# esp32_radio_sch.net
KiCad netlist of a schematic drawn in Altium Designer
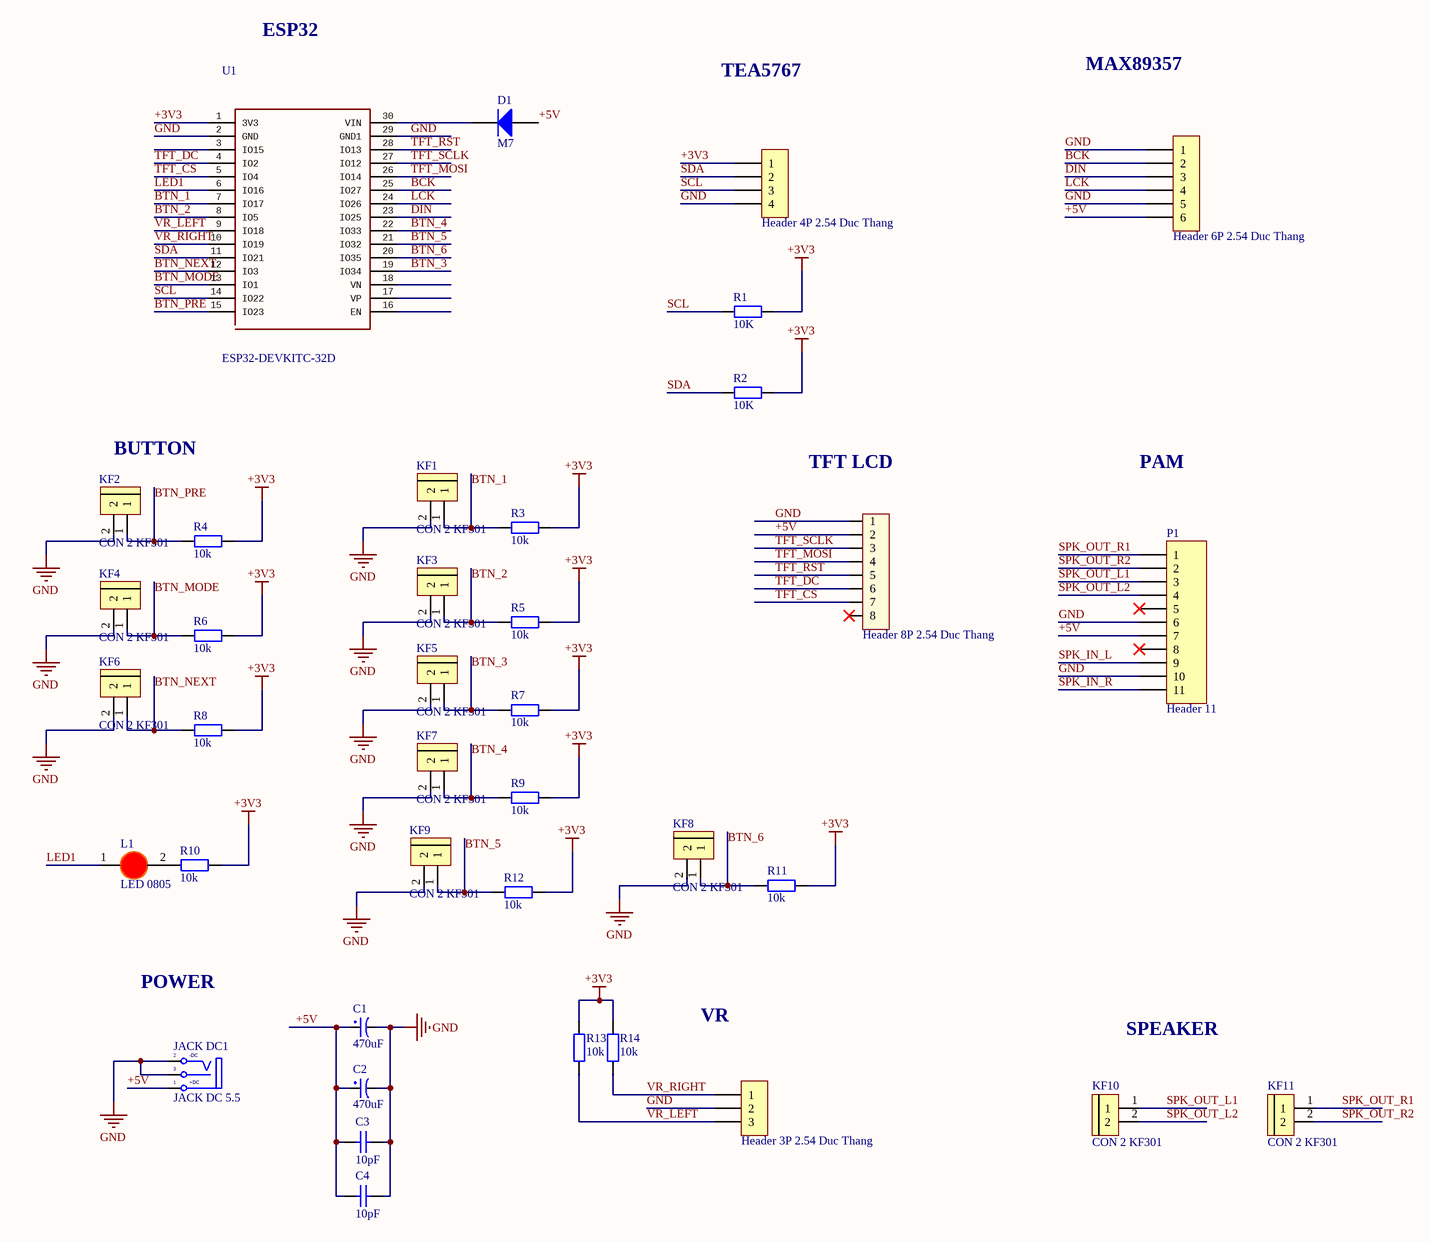
[diagram p0: esp32_radio_sch.SchDoc]

(export (version "E")
  (design (tool "Eeschema 10.0.6"))
  (components
    (comp (ref "C1")
      (value "470uF")
      (footprint "tu tantalum smd7343")
      (description "Dán")
      (libsource (lib "Altium_Lib_by_KhueNguyenCreator") (part "Tu tantalum 470uF 10V SMD7343"))
    )
    (comp (ref "C2")
      (value "470uF")
      (footprint "tu tantalum smd7343")
      (description "Dán")
      (libsource (lib "Altium_Lib_by_KhueNguyenCreator") (part "Tu tantalum 470uF 10V SMD7343"))
    )
    (comp (ref "C3")
      (value "10pF")
      (footprint "tu 0805")
      (description "Dán")
      (libsource (lib "Altium_Lib_by_KhueNguyenCreator") (part "Tu 0805 10pF 50V 10%"))
    )
    (comp (ref "C4")
      (value "10pF")
      (footprint "tu 0805")
      (description "Dán")
      (libsource (lib "Altium_Lib_by_KhueNguyenCreator") (part "Tu 0805 10pF 50V 10%"))
    )
    (comp (ref "D1")
      (value "M7")
      (footprint "DIODE SMA")
      (description "Dán")
      (libsource (lib "Altium_Lib_by_KhueNguyenCreator") (part "Diode M7 ( 4007 )"))
    )
    (comp (ref "H1")
      (value "Header 6P 2.54 Duc Thang")
      (footprint "XH2.54M-6")
      (description "Cắm")
      (libsource (lib "Altium_Lib_by_KhueNguyenCreator") (part "Header 6P 2.54 Duc Thang"))
    )
    (comp (ref "H2")
      (value "Header 4P 2.54 Duc Thang")
      (footprint "XH2.54M-4")
      (description "Cắm")
      (libsource (lib "Altium_Lib_by_KhueNguyenCreator") (part "Header 4P 2.54 Duc Thang"))
    )
    (comp (ref "H3")
      (value "Header 8P 2.54 Duc Thang")
      (footprint "XH2.54M-8")
      (description "Cắm")
      (libsource (lib "Altium_Lib_by_KhueNguyenCreator") (part "Header 8P 2.54 Duc Thang"))
    )
    (comp (ref "H4")
      (value "Header 3P 2.54 Duc Thang")
      (footprint "XH2.54M-3")
      (description "Cắm")
      (libsource (lib "Altium_Lib_by_KhueNguyenCreator") (part "Header 3P 2.54 Duc Thang"))
    )
    (comp (ref "JACK DC1")
      (value "JACK DC 5.5")
      (footprint "JACK DC 5.5")
      (libsource (lib "Altium_Lib_by_KhueNguyenCreator") (part "JACK DC 5.5"))
    )
    (comp (ref "KF1")
      (value "CON 2 KF301")
      (footprint "Nut Nhan 2 Chan SMD 3x6x2.5")
      (description "Cắm")
      (libsource (lib "Altium_Lib_by_KhueNguyenCreator") (part "CON 2 KF301"))
    )
    (comp (ref "KF2")
      (value "CON 2 KF301")
      (footprint "Nut Nhan 2 Chan SMD 3x6x2.5")
      (description "Cắm")
      (libsource (lib "Altium_Lib_by_KhueNguyenCreator") (part "CON 2 KF301"))
    )
    (comp (ref "KF3")
      (value "CON 2 KF301")
      (footprint "Nut Nhan 2 Chan SMD 3x6x2.5")
      (description "Cắm")
      (libsource (lib "Altium_Lib_by_KhueNguyenCreator") (part "CON 2 KF301"))
    )
    (comp (ref "KF4")
      (value "CON 2 KF301")
      (footprint "Nut Nhan 2 Chan SMD 3x6x2.5")
      (description "Cắm")
      (libsource (lib "Altium_Lib_by_KhueNguyenCreator") (part "CON 2 KF301"))
    )
    (comp (ref "KF5")
      (value "CON 2 KF301")
      (footprint "Nut Nhan 2 Chan SMD 3x6x2.5")
      (description "Cắm")
      (libsource (lib "Altium_Lib_by_KhueNguyenCreator") (part "CON 2 KF301"))
    )
    (comp (ref "KF6")
      (value "CON 2 KF301")
      (footprint "Nut Nhan 2 Chan SMD 3x6x2.5")
      (description "Cắm")
      (libsource (lib "Altium_Lib_by_KhueNguyenCreator") (part "CON 2 KF301"))
    )
    (comp (ref "KF7")
      (value "CON 2 KF301")
      (footprint "Nut Nhan 2 Chan SMD 3x6x2.5")
      (description "Cắm")
      (libsource (lib "Altium_Lib_by_KhueNguyenCreator") (part "CON 2 KF301"))
    )
    (comp (ref "KF8")
      (value "CON 2 KF301")
      (footprint "Nut Nhan 2 Chan SMD 3x6x2.5")
      (description "Cắm")
      (libsource (lib "Altium_Lib_by_KhueNguyenCreator") (part "CON 2 KF301"))
    )
    (comp (ref "KF9")
      (value "CON 2 KF301")
      (footprint "Nut Nhan 2 Chan SMD 3x6x2.5")
      (description "Cắm")
      (libsource (lib "Altium_Lib_by_KhueNguyenCreator") (part "CON 2 KF301"))
    )
    (comp (ref "KF10")
      (value "CON 2 KF301")
      (footprint "Con 2 KF301 5.08")
      (description "Cắm")
      (libsource (lib "") (part "CON 2 KF301_1"))
    )
    (comp (ref "KF11")
      (value "CON 2 KF301")
      (footprint "Con 2 KF301 5.08")
      (description "Cắm")
      (libsource (lib "") (part "CON 2 KF301_1"))
    )
    (comp (ref "L1")
      (value "LED 0805")
      (footprint "LED-0805-Red")
      (description "Dán")
      (libsource (lib "Altium_Lib_by_KhueNguyenCreator") (part "LED 0805 Do"))
    )
    (comp (ref "P1")
      (value "Header 11")
      (footprint "Header 11")
      (description "Header, 11-Pin")
      (fields (field (name "PUBLISHER") "Altium Limited"))
      (libsource (lib "Miscellaneous Connectors") (part "Header 11"))
    )
    (comp (ref "R1")
      (value "10K")
      (footprint "tro smd 0805")
      (description "Dán")
      (libsource (lib "Altium_Lib_by_KhueNguyenCreator") (part "Tro 0805 1% 1k"))
    )
    (comp (ref "R2")
      (value "10K")
      (footprint "tro smd 0805")
      (description "Dán")
      (libsource (lib "Altium_Lib_by_KhueNguyenCreator") (part "Tro 0805 1% 1k"))
    )
    (comp (ref "R3")
      (value "10k")
      (footprint "tro smd 0805")
      (description "Dán")
      (libsource (lib "Altium_Lib_by_KhueNguyenCreator") (part "Tro 0805 1% 1k"))
    )
    (comp (ref "R4")
      (value "10k")
      (footprint "tro smd 0805")
      (description "Dán")
      (libsource (lib "Altium_Lib_by_KhueNguyenCreator") (part "Tro 0805 1% 1k"))
    )
    (comp (ref "R5")
      (value "10k")
      (footprint "tro smd 0805")
      (description "Dán")
      (libsource (lib "Altium_Lib_by_KhueNguyenCreator") (part "Tro 0805 1% 1k"))
    )
    (comp (ref "R6")
      (value "10k")
      (footprint "tro smd 0805")
      (description "Dán")
      (libsource (lib "Altium_Lib_by_KhueNguyenCreator") (part "Tro 0805 1% 1k"))
    )
    (comp (ref "R7")
      (value "10k")
      (footprint "tro smd 0805")
      (description "Dán")
      (libsource (lib "Altium_Lib_by_KhueNguyenCreator") (part "Tro 0805 1% 1k"))
    )
    (comp (ref "R8")
      (value "10k")
      (footprint "tro smd 0805")
      (description "Dán")
      (libsource (lib "Altium_Lib_by_KhueNguyenCreator") (part "Tro 0805 1% 1k"))
    )
    (comp (ref "R9")
      (value "10k")
      (footprint "tro smd 0805")
      (description "Dán")
      (libsource (lib "Altium_Lib_by_KhueNguyenCreator") (part "Tro 0805 1% 1k"))
    )
    (comp (ref "R10")
      (value "10k")
      (footprint "tro smd 0805")
      (description "Dán")
      (libsource (lib "Altium_Lib_by_KhueNguyenCreator") (part "Tro 0805 1% 1k"))
    )
    (comp (ref "R11")
      (value "10k")
      (footprint "tro smd 0805")
      (description "Dán")
      (libsource (lib "Altium_Lib_by_KhueNguyenCreator") (part "Tro 0805 1% 1k"))
    )
    (comp (ref "R12")
      (value "10k")
      (footprint "tro smd 0805")
      (description "Dán")
      (libsource (lib "Altium_Lib_by_KhueNguyenCreator") (part "Tro 0805 1% 1k"))
    )
    (comp (ref "R13")
      (value "10k")
      (footprint "tro smd 0805")
      (description "Dán")
      (libsource (lib "Altium_Lib_by_KhueNguyenCreator") (part "Tro 0805 1% 1k"))
    )
    (comp (ref "R14")
      (value "10k")
      (footprint "tro smd 0805")
      (description "Dán")
      (libsource (lib "Altium_Lib_by_KhueNguyenCreator") (part "Tro 0805 1% 1k"))
    )
    (comp (ref "U1")
      (value "ESP32-DEVKITC-32D")
      (footprint "MODULE_ESP32-DEVKITV1")
      (description "Eval Board For Esp-Wroom-32")
      (fields (field (name "MF") "Espressif Systems"))
      (libsource (lib "AltiumLibraryDDT") (part "ESP32-DEVKITC-32D"))
    )
  )
  (nets
    (net (code "1") (name "+3V3") (class "Default")
      (node (ref "H2") (pin "1") (pinfunction "1_1") (pintype "passive"))
      (node (ref "R1") (pin "2") (pinfunction "2_2") (pintype "passive"))
      (node (ref "R10") (pin "2") (pinfunction "2_2") (pintype "passive"))
      (node (ref "R11") (pin "2") (pinfunction "2_2") (pintype "passive"))
      (node (ref "R12") (pin "2") (pinfunction "2_2") (pintype "passive"))
      (node (ref "R13") (pin "2") (pinfunction "2_2") (pintype "passive"))
      (node (ref "R14") (pin "2") (pinfunction "2_2") (pintype "passive"))
      (node (ref "R2") (pin "2") (pinfunction "2_2") (pintype "passive"))
      (node (ref "R3") (pin "2") (pinfunction "2_2") (pintype "passive"))
      (node (ref "R4") (pin "2") (pinfunction "2_2") (pintype "passive"))
      (node (ref "R5") (pin "2") (pinfunction "2_2") (pintype "passive"))
      (node (ref "R6") (pin "2") (pinfunction "2_2") (pintype "passive"))
      (node (ref "R7") (pin "2") (pinfunction "2_2") (pintype "passive"))
      (node (ref "R8") (pin "2") (pinfunction "2_2") (pintype "passive"))
      (node (ref "R9") (pin "2") (pinfunction "2_2") (pintype "passive"))
      (node (ref "U1") (pin "1") (pinfunction "3V3_1") (pintype "passive"))
    )
    (net (code "2") (name "/+5V") (class "Default")
      (node (ref "C1") (pin "1") (pinfunction "1_1") (pintype "passive"))
      (node (ref "C2") (pin "1") (pinfunction "1_1") (pintype "passive"))
      (node (ref "C3") (pin "2") (pinfunction "2_2") (pintype "passive"))
      (node (ref "C4") (pin "2") (pinfunction "2_2") (pintype "passive"))
      (node (ref "D1") (pin "1") (pinfunction "A_1") (pintype "passive"))
      (node (ref "H1") (pin "6") (pinfunction "6_6") (pintype "passive"))
      (node (ref "H3") (pin "2") (pinfunction "2_2") (pintype "passive"))
      (node (ref "JACK DC1") (pin "1") (pinfunction "T_1") (pintype "passive"))
      (node (ref "P1") (pin "7") (pinfunction "7_7") (pintype "passive"))
    )
    (net (code "3") (name "/BCK") (class "Default")
      (node (ref "H1") (pin "2") (pinfunction "2_2") (pintype "passive"))
      (node (ref "U1") (pin "25") (pinfunction "IO27_25") (pintype "passive"))
    )
    (net (code "4") (name "/BTN_1") (class "Default")
      (node (ref "KF1") (pin "1") (pinfunction "1_1") (pintype "passive"))
      (node (ref "R3") (pin "1") (pinfunction "1_1") (pintype "passive"))
      (node (ref "U1") (pin "7") (pinfunction "IO17_7") (pintype "passive"))
    )
    (net (code "5") (name "/BTN_2") (class "Default")
      (node (ref "KF3") (pin "1") (pinfunction "1_1") (pintype "passive"))
      (node (ref "R5") (pin "1") (pinfunction "1_1") (pintype "passive"))
      (node (ref "U1") (pin "8") (pinfunction "IO5_8") (pintype "passive"))
    )
    (net (code "6") (name "/BTN_3") (class "Default")
      (node (ref "KF5") (pin "1") (pinfunction "1_1") (pintype "passive"))
      (node (ref "R7") (pin "1") (pinfunction "1_1") (pintype "passive"))
      (node (ref "U1") (pin "19") (pinfunction "IO34_19") (pintype "passive"))
    )
    (net (code "7") (name "/BTN_4") (class "Default")
      (node (ref "KF7") (pin "1") (pinfunction "1_1") (pintype "passive"))
      (node (ref "R9") (pin "1") (pinfunction "1_1") (pintype "passive"))
      (node (ref "U1") (pin "22") (pinfunction "IO33_22") (pintype "passive"))
    )
    (net (code "8") (name "/BTN_5") (class "Default")
      (node (ref "KF9") (pin "1") (pinfunction "1_1") (pintype "passive"))
      (node (ref "R12") (pin "1") (pinfunction "1_1") (pintype "passive"))
      (node (ref "U1") (pin "21") (pinfunction "IO32_21") (pintype "passive"))
    )
    (net (code "9") (name "/BTN_6") (class "Default")
      (node (ref "KF8") (pin "1") (pinfunction "1_1") (pintype "passive"))
      (node (ref "R11") (pin "1") (pinfunction "1_1") (pintype "passive"))
      (node (ref "U1") (pin "20") (pinfunction "IO35_20") (pintype "passive"))
    )
    (net (code "10") (name "/BTN_MODE") (class "Default")
      (node (ref "KF4") (pin "1") (pinfunction "1_1") (pintype "passive"))
      (node (ref "R6") (pin "1") (pinfunction "1_1") (pintype "passive"))
      (node (ref "U1") (pin "13") (pinfunction "IO1_13") (pintype "passive"))
    )
    (net (code "11") (name "/BTN_NEXT") (class "Default")
      (node (ref "KF6") (pin "1") (pinfunction "1_1") (pintype "passive"))
      (node (ref "R8") (pin "1") (pinfunction "1_1") (pintype "passive"))
      (node (ref "U1") (pin "12") (pinfunction "IO3_12") (pintype "passive"))
    )
    (net (code "12") (name "/BTN_PRE") (class "Default")
      (node (ref "KF2") (pin "1") (pinfunction "1_1") (pintype "passive"))
      (node (ref "R4") (pin "1") (pinfunction "1_1") (pintype "passive"))
      (node (ref "U1") (pin "15") (pinfunction "IO23_15") (pintype "passive"))
    )
    (net (code "13") (name "/DIN") (class "Default")
      (node (ref "H1") (pin "3") (pinfunction "3_3") (pintype "passive"))
      (node (ref "U1") (pin "23") (pinfunction "IO25_23") (pintype "passive"))
    )
    (net (code "14") (name "/LCK") (class "Default")
      (node (ref "H1") (pin "4") (pinfunction "4_4") (pintype "passive"))
      (node (ref "U1") (pin "24") (pinfunction "IO26_24") (pintype "passive"))
    )
    (net (code "15") (name "/LED1") (class "Default")
      (node (ref "L1") (pin "1") (pinfunction "A_1") (pintype "passive"))
      (node (ref "U1") (pin "6") (pinfunction "IO16_6") (pintype "passive"))
    )
    (net (code "16") (name "/SCL") (class "Default")
      (node (ref "H2") (pin "3") (pinfunction "3_3") (pintype "passive"))
      (node (ref "R1") (pin "1") (pinfunction "1_1") (pintype "passive"))
      (node (ref "U1") (pin "14") (pinfunction "IO22_14") (pintype "passive"))
    )
    (net (code "17") (name "/SDA") (class "Default")
      (node (ref "H2") (pin "2") (pinfunction "2_2") (pintype "passive"))
      (node (ref "R2") (pin "1") (pinfunction "1_1") (pintype "passive"))
      (node (ref "U1") (pin "11") (pinfunction "IO21_11") (pintype "passive"))
    )
    (net (code "18") (name "/SPK_IN_L") (class "Default")
      (node (ref "P1") (pin "9") (pinfunction "9_9") (pintype "passive"))
    )
    (net (code "19") (name "/SPK_IN_R") (class "Default")
      (node (ref "P1") (pin "11") (pinfunction "11_11") (pintype "passive"))
    )
    (net (code "20") (name "/SPK_OUT_L1") (class "Default")
      (node (ref "KF10") (pin "1") (pinfunction "1_1") (pintype "passive"))
      (node (ref "P1") (pin "3") (pinfunction "3_3") (pintype "passive"))
    )
    (net (code "21") (name "/SPK_OUT_L2") (class "Default")
      (node (ref "KF10") (pin "2") (pinfunction "2_2") (pintype "passive"))
      (node (ref "P1") (pin "4") (pinfunction "4_4") (pintype "passive"))
    )
    (net (code "22") (name "/SPK_OUT_R1") (class "Default")
      (node (ref "KF11") (pin "1") (pinfunction "1_1") (pintype "passive"))
      (node (ref "P1") (pin "1") (pinfunction "1_1") (pintype "passive"))
    )
    (net (code "23") (name "/SPK_OUT_R2") (class "Default")
      (node (ref "KF11") (pin "2") (pinfunction "2_2") (pintype "passive"))
      (node (ref "P1") (pin "2") (pinfunction "2_2") (pintype "passive"))
    )
    (net (code "24") (name "/TFT_CS") (class "Default")
      (node (ref "H3") (pin "7") (pinfunction "7_7") (pintype "passive"))
      (node (ref "U1") (pin "5") (pinfunction "IO4_5") (pintype "passive"))
    )
    (net (code "25") (name "/TFT_DC") (class "Default")
      (node (ref "H3") (pin "6") (pinfunction "6_6") (pintype "passive"))
      (node (ref "U1") (pin "4") (pinfunction "IO2_4") (pintype "passive"))
    )
    (net (code "26") (name "/TFT_MOSI") (class "Default")
      (node (ref "H3") (pin "4") (pinfunction "4_4") (pintype "passive"))
      (node (ref "U1") (pin "26") (pinfunction "IO14_26") (pintype "passive"))
    )
    (net (code "27") (name "/TFT_RST") (class "Default")
      (node (ref "H3") (pin "5") (pinfunction "5_5") (pintype "passive"))
      (node (ref "U1") (pin "28") (pinfunction "IO13_28") (pintype "passive"))
    )
    (net (code "28") (name "/TFT_SCLK") (class "Default")
      (node (ref "H3") (pin "3") (pinfunction "3_3") (pintype "passive"))
      (node (ref "U1") (pin "27") (pinfunction "IO12_27") (pintype "passive"))
    )
    (net (code "29") (name "/VR_LEFT") (class "Default")
      (node (ref "H4") (pin "3") (pinfunction "3_3") (pintype "passive"))
      (node (ref "R13") (pin "1") (pinfunction "1_1") (pintype "passive"))
      (node (ref "U1") (pin "9") (pinfunction "IO18_9") (pintype "passive"))
    )
    (net (code "30") (name "/VR_RIGHT") (class "Default")
      (node (ref "H4") (pin "1") (pinfunction "1_1") (pintype "passive"))
      (node (ref "R14") (pin "1") (pinfunction "1_1") (pintype "passive"))
      (node (ref "U1") (pin "10") (pinfunction "IO19_10") (pintype "passive"))
    )
    (net (code "31") (name "GND") (class "Default")
      (node (ref "C1") (pin "2") (pinfunction "2_2") (pintype "passive"))
      (node (ref "C2") (pin "2") (pinfunction "2_2") (pintype "passive"))
      (node (ref "C3") (pin "1") (pinfunction "1_1") (pintype "passive"))
      (node (ref "C4") (pin "1") (pinfunction "1_1") (pintype "passive"))
      (node (ref "H1") (pin "1") (pinfunction "1_1") (pintype "passive"))
      (node (ref "H1") (pin "5") (pinfunction "5_5") (pintype "passive"))
      (node (ref "H2") (pin "4") (pinfunction "4_4") (pintype "passive"))
      (node (ref "H3") (pin "1") (pinfunction "1_1") (pintype "passive"))
      (node (ref "H4") (pin "2") (pinfunction "2_2") (pintype "passive"))
      (node (ref "JACK DC1") (pin "2") (pinfunction "TN_2") (pintype "passive"))
      (node (ref "JACK DC1") (pin "3") (pinfunction "S_3") (pintype "power_in"))
      (node (ref "KF1") (pin "2") (pinfunction "2_2") (pintype "passive"))
      (node (ref "KF2") (pin "2") (pinfunction "2_2") (pintype "passive"))
      (node (ref "KF3") (pin "2") (pinfunction "2_2") (pintype "passive"))
      (node (ref "KF4") (pin "2") (pinfunction "2_2") (pintype "passive"))
      (node (ref "KF5") (pin "2") (pinfunction "2_2") (pintype "passive"))
      (node (ref "KF6") (pin "2") (pinfunction "2_2") (pintype "passive"))
      (node (ref "KF7") (pin "2") (pinfunction "2_2") (pintype "passive"))
      (node (ref "KF8") (pin "2") (pinfunction "2_2") (pintype "passive"))
      (node (ref "KF9") (pin "2") (pinfunction "2_2") (pintype "passive"))
      (node (ref "P1") (pin "10") (pinfunction "10_10") (pintype "passive"))
      (node (ref "P1") (pin "6") (pinfunction "6_6") (pintype "passive"))
      (node (ref "U1") (pin "2") (pinfunction "GND_2") (pintype "passive"))
      (node (ref "U1") (pin "29") (pinfunction "GND1_29") (pintype "passive"))
    )
    (net (code "32") (name "Net-(D1-K)") (class "Default")
      (node (ref "D1") (pin "2") (pinfunction "K_2") (pintype "passive"))
      (node (ref "U1") (pin "30") (pinfunction "VIN_30") (pintype "passive"))
    )
    (net (code "33") (name "Net-(L1-K)") (class "Default")
      (node (ref "L1") (pin "2") (pinfunction "K_2") (pintype "passive"))
      (node (ref "R10") (pin "1") (pinfunction "1_1") (pintype "passive"))
    )
    (net (code "34") (name "unconnected-(H3-Pad8)") (class "Default")
      (node (ref "H3") (pin "8") (pinfunction "8_8") (pintype "passive+no_connect"))
    )
    (net (code "35") (name "unconnected-(P1-Pad5)") (class "Default")
      (node (ref "P1") (pin "5") (pinfunction "5_5") (pintype "passive+no_connect"))
    )
    (net (code "36") (name "unconnected-(P1-Pad8)") (class "Default")
      (node (ref "P1") (pin "8") (pinfunction "8_8") (pintype "passive+no_connect"))
    )
    (net (code "37") (name "unconnected-(U1-EN-Pad16)") (class "Default")
      (node (ref "U1") (pin "16") (pinfunction "EN_16") (pintype "passive"))
    )
    (net (code "38") (name "unconnected-(U1-IO15-Pad3)") (class "Default")
      (node (ref "U1") (pin "3") (pinfunction "IO15_3") (pintype "passive"))
    )
    (net (code "39") (name "unconnected-(U1-VN-Pad18)") (class "Default")
      (node (ref "U1") (pin "18") (pinfunction "VN_18") (pintype "passive"))
    )
    (net (code "40") (name "unconnected-(U1-VP-Pad17)") (class "Default")
      (node (ref "U1") (pin "17") (pinfunction "VP_17") (pintype "passive"))
    )
  )
)
